# Power.net
KiCad netlist of a schematic drawn in Altium Designer
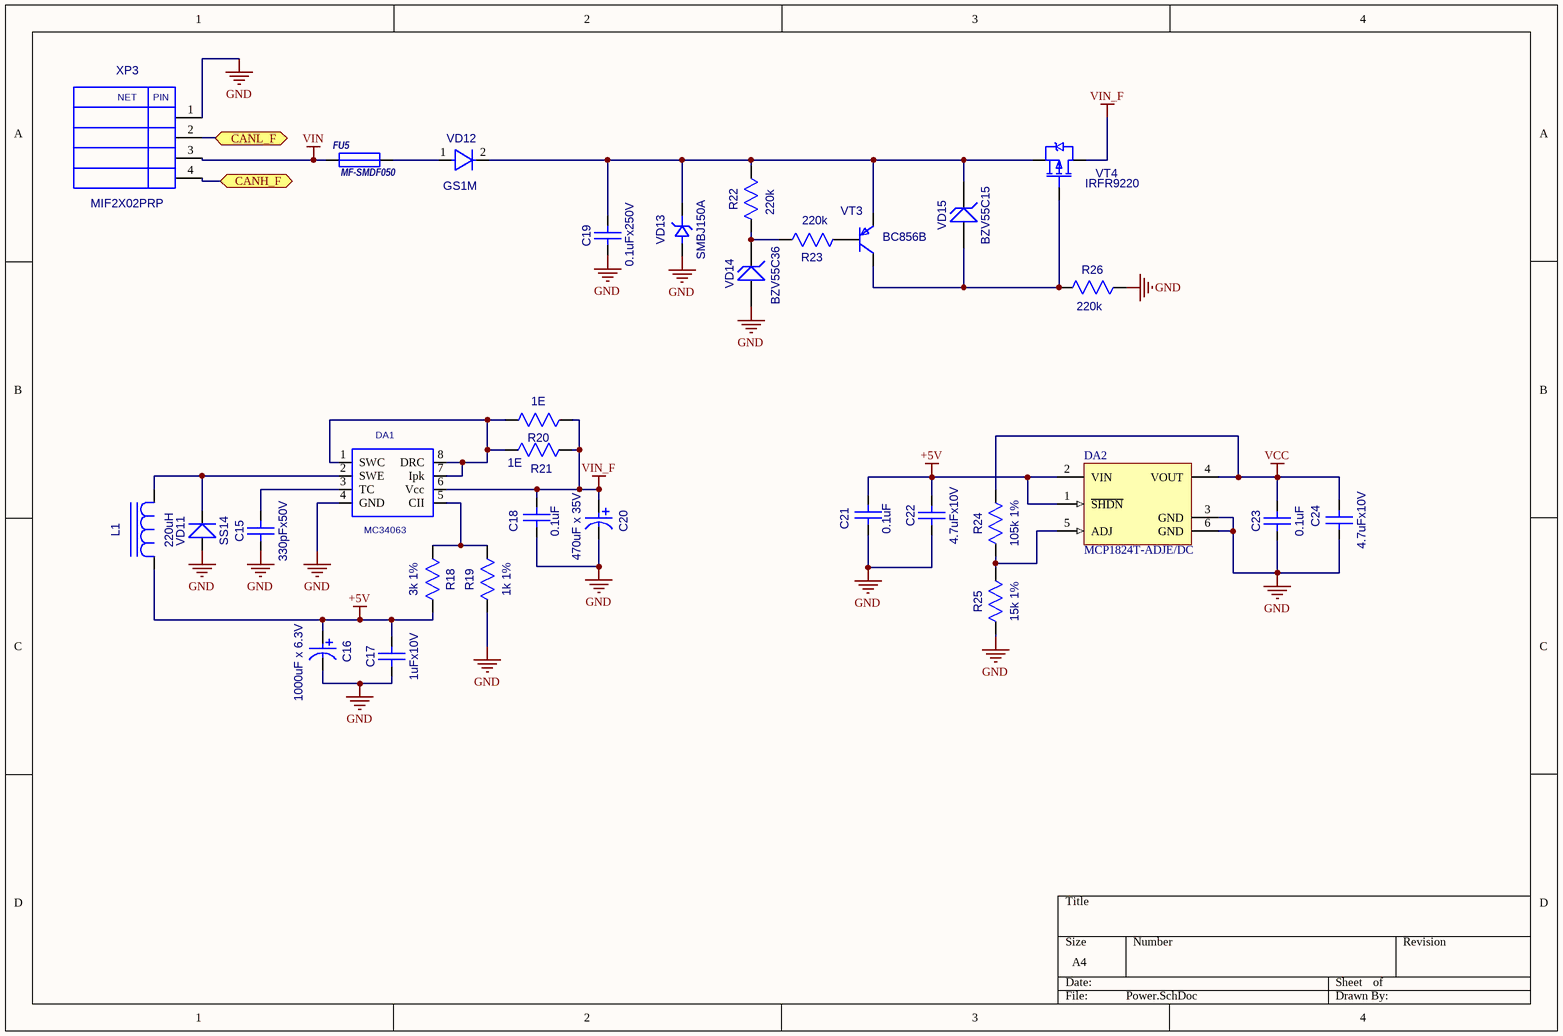
[diagram p0: Power.SchDoc]

(export (version "E")
  (design (tool "Eeschema 10.0.6"))
  (components
    (comp (ref "C15")
      (value "330pFx50V")
      (footprint "CC0603-3M")
      (description "CC0603")
      (libsource (lib "gprs_modem") (part "CC0603"))
    )
    (comp (ref "C16")
      (value "1000uF x 6.3V")
      (footprint "CC8X3.5")
      (description "CAP0.35")
      (libsource (lib "gprs_modem") (part "CAP0.35"))
    )
    (comp (ref "C17")
      (value "1uFx10V")
      (footprint "CC0603-3M")
      (description "CC0603")
      (libsource (lib "gprs_modem") (part "CC0603"))
    )
    (comp (ref "C18")
      (value "0.1uF")
      (footprint "CC0603-3M")
      (description "CC0603")
      (libsource (lib "gprs_modem") (part "CC0603"))
    )
    (comp (ref "C19")
      (value "0.1uFx250V")
      (footprint "CC1206-MIDI")
      (description "CC1206")
      (libsource (lib "gprs_modem") (part "CC1206"))
    )
    (comp (ref "C20")
      (value "470uF x 35V")
      (footprint "CC16X10_CAP0.5(1)(Primary)")
      (description "CAP0.5(1)")
      (libsource (lib "gprs_modem") (part "CAP0.5(1)"))
    )
    (comp (ref "C21")
      (value "0.1uF")
      (footprint "CC0603-3M")
      (description "CC0603")
      (libsource (lib "gprs_modem") (part "CC0603"))
    )
    (comp (ref "C22")
      (value "4.7uFx10V")
      (footprint "CC0805-MIDI-2M1")
      (description "CC0805")
      (libsource (lib "gprs_modem") (part "CC0805"))
    )
    (comp (ref "C23")
      (value "0.1uF")
      (footprint "CC0603-3M")
      (description "CC0603")
      (libsource (lib "gprs_modem") (part "CC0603"))
    )
    (comp (ref "C24")
      (value "4.7uFx10V")
      (footprint "CC0805-MIDI-2M1")
      (description "CC0805")
      (libsource (lib "gprs_modem") (part "CC0805"))
    )
    (comp (ref "DA1") (value "MC34063") (footprint "SO-8") (libsource (lib "Schetchik") (part "MC34063")))
    (comp (ref "DA2")
      (value "MCP1824T-ADJE/DC")
      (footprint "SOT223-6")
      (fields (field (name "PUBLISHER") "Altium Limited"))
      (libsource (lib "gprs_modem") (part "MCP1824T-ADJE/DC"))
    )
    (comp (ref "FU5")
      (value "MF-SMDF050")
      (footprint "MF-SMDF")
      (description "MF-SMDF")
      (libsource (lib "gprs_modem") (part "MF-SMDF"))
    )
    (comp (ref "L1")
      (value "220uH")
      (footprint "SDR0805")
      (description "SDR0805")
      (libsource (lib "gprs_modem") (part "SDR0805"))
    )
    (comp (ref "R18")
      (value "3k 1%")
      (footprint "RC0603-3M")
      (description "RC0603")
      (libsource (lib "gprs_modem") (part "RC0603"))
    )
    (comp (ref "R19")
      (value "1k 1%")
      (footprint "RC0603-3M")
      (description "RC0603")
      (libsource (lib "gprs_modem") (part "RC0603"))
    )
    (comp (ref "R20")
      (value "1E")
      (footprint "RC0805_IPC_NOM")
      (description "RC0805")
      (libsource (lib "gprs_modem") (part "RC0805"))
    )
    (comp (ref "R21")
      (value "1E")
      (footprint "RC0805_IPC_NOM")
      (description "RC0805")
      (libsource (lib "gprs_modem") (part "RC0805"))
    )
    (comp (ref "R22")
      (value "220k")
      (footprint "RC1206-2M")
      (description "RC1206")
      (libsource (lib "gprs_modem") (part "RC1206"))
    )
    (comp (ref "R23")
      (value "220k")
      (footprint "RC1206-2M")
      (description "RC1206")
      (libsource (lib "gprs_modem") (part "RC1206"))
    )
    (comp (ref "R24")
      (value "105k 1%")
      (footprint "RC0603-3M")
      (description "RC0603")
      (libsource (lib "gprs_modem") (part "RC0603"))
    )
    (comp (ref "R25")
      (value "15k 1%")
      (footprint "RC0603-3M")
      (description "RC0603")
      (libsource (lib "gprs_modem") (part "RC0603"))
    )
    (comp (ref "R26")
      (value "220k")
      (footprint "RC1206-2M")
      (description "RC1206")
      (libsource (lib "gprs_modem") (part "RC1206"))
    )
    (comp (ref "VD11")
      (value "SS14")
      (footprint "SMA")
      (description "Schottky Rectifier")
      (libsource (lib "gprs_modem") (part "SS14"))
    )
    (comp (ref "VD12") (value "GS1M") (footprint "SMA") (libsource (lib "Schetchik") (part "GS1M")))
    (comp (ref "VD13")
      (value "SMBJ150A")
      (footprint "SMB")
      (description "SMBJ")
      (libsource (lib "gprs_modem") (part "SMBJ"))
    )
    (comp (ref "VD14")
      (value "BZV55C36")
      (footprint "SOD-80")
      (description "Zener Voltage Regulator Diode")
      (libsource (lib "gprs_modem") (part "BZV55C12"))
    )
    (comp (ref "VD15")
      (value "BZV55C15")
      (footprint "SOD-80")
      (description "Zener Voltage Regulator Diode")
      (libsource (lib "gprs_modem") (part "BZV55C12"))
    )
    (comp (ref "VT3")
      (value "BC856B")
      (footprint "SOT-23(123)")
      (libsource (lib "Schetchik") (part "BC856B"))
    )
    (comp (ref "VT4")
      (value "IRFR9220")
      (footprint "D-PAK(TO-252AA)")
      (description "HEXFET Power MOSFET")
      (libsource (lib "gprs_modem") (part "IRFR9220"))
    )
    (comp (ref "XP3")
      (value "MIF2X02PRP")
      (footprint "MIF2X02PRP")
      (libsource (lib "Schetchik") (part "MIF2X02PRP"))
    )
  )
  (nets
    (net (code "1") (name "+5V") (class "Default")
      (node (ref "C16") (pin "1") (pintype "passive"))
      (node (ref "C17") (pin "2") (pinfunction "B_2") (pintype "passive"))
      (node (ref "C21") (pin "1") (pinfunction "A_1") (pintype "passive"))
      (node (ref "C22") (pin "2") (pinfunction "B_2") (pintype "passive"))
      (node (ref "DA2") (pin "1") (pinfunction "~{SHDN}_1") (pintype "input"))
      (node (ref "DA2") (pin "2") (pinfunction "VIN_2") (pintype "power_in"))
      (node (ref "L1") (pin "1") (pinfunction "C_1") (pintype "passive"))
      (node (ref "R18") (pin "2") (pinfunction "B_2") (pintype "passive"))
    )
    (net (code "2") (name "/CANH_F") (class "Default")
      (node (ref "XP3") (pin "4") (pinfunction "4_4") (pintype "passive"))
    )
    (net (code "3") (name "/CANL_F") (class "Default")
      (node (ref "XP3") (pin "2") (pinfunction "2_2") (pintype "passive"))
    )
    (net (code "4") (name "GND") (class "Default")
      (node (ref "C15") (pin "1") (pinfunction "A_1") (pintype "passive"))
      (node (ref "C16") (pin "2") (pintype "passive"))
      (node (ref "C17") (pin "1") (pinfunction "A_1") (pintype "passive"))
      (node (ref "C18") (pin "2") (pinfunction "B_2") (pintype "passive"))
      (node (ref "C19") (pin "1") (pinfunction "A_1") (pintype "passive"))
      (node (ref "C20") (pin "1") (pintype "passive"))
      (node (ref "C21") (pin "2") (pinfunction "B_2") (pintype "passive"))
      (node (ref "C22") (pin "1") (pinfunction "A_1") (pintype "passive"))
      (node (ref "C23") (pin "1") (pinfunction "A_1") (pintype "passive"))
      (node (ref "C24") (pin "1") (pinfunction "A_1") (pintype "passive"))
      (node (ref "DA1") (pin "4") (pinfunction "GND_4") (pintype "passive"))
      (node (ref "DA2") (pin "3") (pinfunction "GND_3") (pintype "power_in"))
      (node (ref "DA2") (pin "6") (pinfunction "GND_6") (pintype "power_in"))
      (node (ref "R19") (pin "1") (pinfunction "A_1") (pintype "passive"))
      (node (ref "R25") (pin "1") (pinfunction "A_1") (pintype "passive"))
      (node (ref "R26") (pin "2") (pinfunction "B_2") (pintype "passive"))
      (node (ref "VD11") (pin "1") (pinfunction "A_1") (pintype "passive"))
      (node (ref "VD13") (pin "1") (pinfunction "A_1") (pintype "passive"))
      (node (ref "VD14") (pin "1") (pinfunction "A_1") (pintype "passive"))
      (node (ref "XP3") (pin "1") (pinfunction "1_1") (pintype "passive"))
    )
    (net (code "5") (name "Net-(C15-B)") (class "Default")
      (node (ref "C15") (pin "2") (pinfunction "B_2") (pintype "passive"))
      (node (ref "DA1") (pin "3") (pinfunction "TC_3") (pintype "passive"))
    )
    (net (code "6") (name "Net-(C19-B)") (class "Default")
      (node (ref "C19") (pin "2") (pinfunction "B_2") (pintype "passive"))
      (node (ref "R22") (pin "2") (pinfunction "B_2") (pintype "passive"))
      (node (ref "VD12") (pin "2") (pinfunction "K_2") (pintype "passive"))
      (node (ref "VD13") (pin "2") (pinfunction "K_2") (pintype "passive"))
      (node (ref "VD15") (pin "2") (pintype "passive"))
      (node (ref "VT3") (pin "2") (pinfunction "E_2") (pintype "passive"))
      (node (ref "VT4") (pin "2") (pinfunction "S_2") (pintype "passive"))
    )
    (net (code "7") (name "Net-(DA1-CII)") (class "Default")
      (node (ref "DA1") (pin "5") (pinfunction "CII_5") (pintype "passive"))
      (node (ref "R18") (pin "1") (pinfunction "A_1") (pintype "passive"))
      (node (ref "R19") (pin "2") (pinfunction "B_2") (pintype "passive"))
    )
    (net (code "8") (name "Net-(DA1-DRC)") (class "Default")
      (node (ref "DA1") (pin "1") (pinfunction "SWC_1") (pintype "passive"))
      (node (ref "DA1") (pin "7") (pinfunction "Ipk_7") (pintype "passive"))
      (node (ref "DA1") (pin "8") (pinfunction "DRC_8") (pintype "passive"))
      (node (ref "R20") (pin "2") (pinfunction "B_2") (pintype "passive"))
      (node (ref "R21") (pin "2") (pinfunction "B_2") (pintype "passive"))
    )
    (net (code "9") (name "Net-(DA1-SWE)") (class "Default")
      (node (ref "DA1") (pin "2") (pinfunction "SWE_2") (pintype "passive"))
      (node (ref "L1") (pin "2") (pinfunction "A_2") (pintype "passive"))
      (node (ref "VD11") (pin "2") (pinfunction "K_2") (pintype "passive"))
    )
    (net (code "10") (name "Net-(DA2-ADJ)") (class "Default")
      (node (ref "DA2") (pin "5") (pinfunction "ADJ_5") (pintype "input"))
      (node (ref "R24") (pin "1") (pinfunction "A_1") (pintype "passive"))
      (node (ref "R25") (pin "2") (pinfunction "B_2") (pintype "passive"))
    )
    (net (code "11") (name "Net-(R22-A)") (class "Default")
      (node (ref "R22") (pin "1") (pinfunction "A_1") (pintype "passive"))
      (node (ref "R23") (pin "2") (pinfunction "B_2") (pintype "passive"))
      (node (ref "VD14") (pin "2") (pintype "passive"))
    )
    (net (code "12") (name "Net-(R23-A)") (class "Default")
      (node (ref "R23") (pin "1") (pinfunction "A_1") (pintype "passive"))
      (node (ref "VT3") (pin "1") (pinfunction "B_1") (pintype "passive"))
    )
    (net (code "13") (name "Net-(R26-A)") (class "Default")
      (node (ref "R26") (pin "1") (pinfunction "A_1") (pintype "passive"))
      (node (ref "VD15") (pin "1") (pinfunction "A_1") (pintype "passive"))
      (node (ref "VT3") (pin "3") (pinfunction "C_3") (pintype "passive"))
      (node (ref "VT4") (pin "1") (pinfunction "G_1") (pintype "passive"))
    )
    (net (code "14") (name "Net-(VD12-A)") (class "Default")
      (node (ref "FU5") (pin "2") (pintype "passive"))
      (node (ref "VD12") (pin "1") (pinfunction "A_1") (pintype "passive"))
    )
    (net (code "15") (name "VCC") (class "Default")
      (node (ref "C23") (pin "2") (pinfunction "B_2") (pintype "passive"))
      (node (ref "C24") (pin "2") (pinfunction "B_2") (pintype "passive"))
      (node (ref "DA2") (pin "4") (pinfunction "VOUT_4") (pintype "power_in"))
      (node (ref "R24") (pin "2") (pinfunction "B_2") (pintype "passive"))
    )
    (net (code "16") (name "VIN") (class "Default")
      (node (ref "FU5") (pin "1") (pintype "passive"))
      (node (ref "XP3") (pin "3") (pinfunction "3_3") (pintype "passive"))
    )
    (net (code "17") (name "VIN_F") (class "Default")
      (node (ref "C18") (pin "1") (pinfunction "A_1") (pintype "passive"))
      (node (ref "C20") (pin "2") (pintype "passive"))
      (node (ref "DA1") (pin "6") (pinfunction "Vcc_6") (pintype "passive"))
      (node (ref "R20") (pin "1") (pinfunction "A_1") (pintype "passive"))
      (node (ref "R21") (pin "1") (pinfunction "A_1") (pintype "passive"))
      (node (ref "VT4") (pin "3") (pinfunction "D_3") (pintype "passive"))
    )
  )
)
